# tcrt_mux.net
KiCad netlist of a schematic drawn in Altium Designer
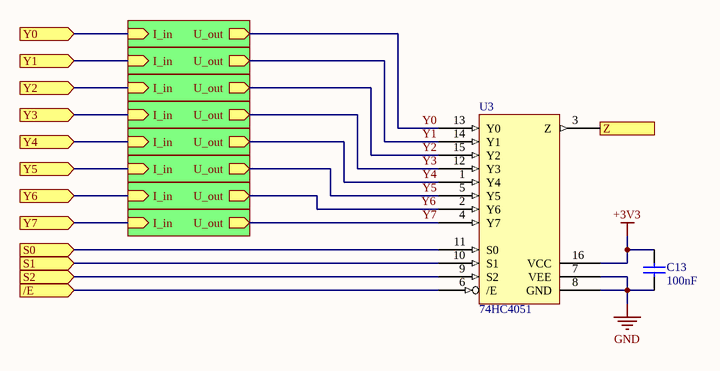
[diagram p0: tcrt_mux.SchDoc]

(export (version "E")
  (design (tool "Eeschema 10.0.6"))
  (components
    (comp (ref "C13")
      (value "100nF")
      (footprint "FP_0805_CAP_085")
      (description "Capacitor")
      (fields (field (name "VOLTAGE") "50V"))
      (libsource (lib "hallglib-2018") (part "CAP 100nF"))
    )
    (comp (ref "U3")
      (value "74HC4051")
      (footprint "SOP16")
      (description "Analog multiplexer")
      (libsource (lib "mb") (part "74HC4051"))
    )
  )
  (nets
    (net (code "1") (name "+3V3") (class "Default")
      (node (ref "C13") (pin "2") (pinfunction "2_2") (pintype "passive"))
      (node (ref "U3") (pin "16") (pinfunction "VCC_16") (pintype "power_in"))
    )
    (net (code "2") (name "/S0") (class "Default")
      (node (ref "U3") (pin "11") (pinfunction "S0_11") (pintype "input"))
    )
    (net (code "3") (name "/S1") (class "Default")
      (node (ref "U3") (pin "10") (pinfunction "S1_10") (pintype "input"))
    )
    (net (code "4") (name "/S2") (class "Default")
      (node (ref "U3") (pin "9") (pinfunction "S2_9") (pintype "input"))
    )
    (net (code "5") (name "/Y0") (class "Default")
      (node (ref "U3") (pin "13") (pinfunction "Y0_13") (pintype "input"))
    )
    (net (code "6") (name "/Y1") (class "Default")
      (node (ref "U3") (pin "14") (pinfunction "Y1_14") (pintype "input"))
    )
    (net (code "7") (name "/Y2") (class "Default")
      (node (ref "U3") (pin "15") (pinfunction "Y2_15") (pintype "input"))
    )
    (net (code "8") (name "/Y3") (class "Default")
      (node (ref "U3") (pin "12") (pinfunction "Y3_12") (pintype "input"))
    )
    (net (code "9") (name "/Y4") (class "Default")
      (node (ref "U3") (pin "1") (pinfunction "Y4_1") (pintype "input"))
    )
    (net (code "10") (name "/Y5") (class "Default")
      (node (ref "U3") (pin "5") (pinfunction "Y5_5") (pintype "input"))
    )
    (net (code "11") (name "/Y6") (class "Default")
      (node (ref "U3") (pin "2") (pinfunction "Y6_2") (pintype "input"))
    )
    (net (code "12") (name "/Y7") (class "Default")
      (node (ref "U3") (pin "4") (pinfunction "Y7_4") (pintype "input"))
    )
    (net (code "13") (name "/Z") (class "Default")
      (node (ref "U3") (pin "3") (pinfunction "Z_3") (pintype "output"))
    )
    (net (code "14") (name "/{slash}E") (class "Default")
      (node (ref "U3") (pin "6") (pinfunction "/E_6") (pintype "input"))
    )
    (net (code "15") (name "GND") (class "Default")
      (node (ref "C13") (pin "1") (pinfunction "1_1") (pintype "passive"))
      (node (ref "U3") (pin "7") (pinfunction "VEE_7") (pintype "power_in"))
      (node (ref "U3") (pin "8") (pinfunction "GND_8") (pintype "power_in"))
    )
  )
)
